# shield_uno.net
KiCad netlist of a schematic drawn in EAGLE
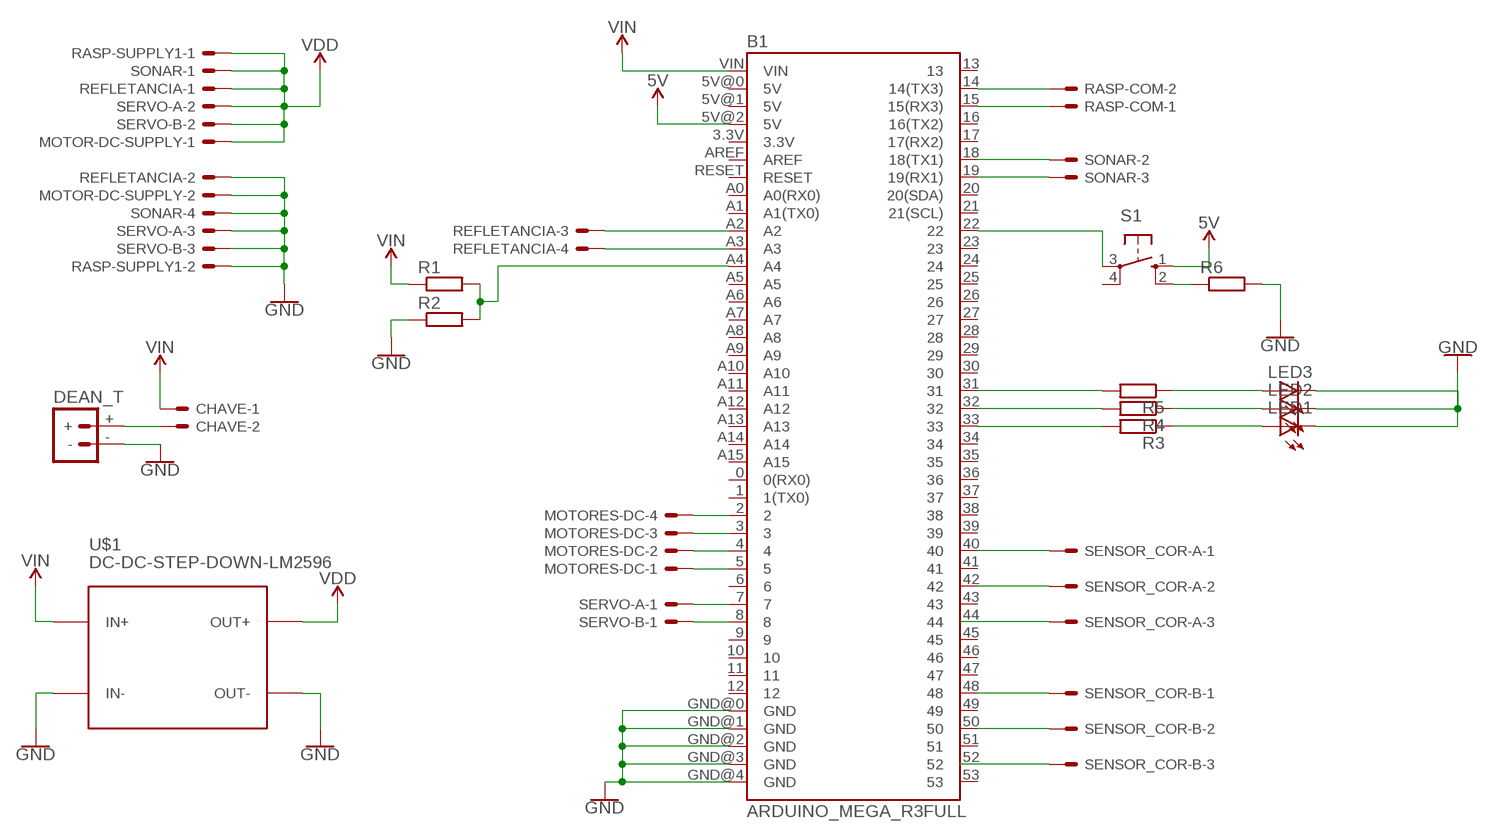
[diagram p0: schematic, sheet 1]

(export (version "E")
  (design (tool "Eeschema 10.0.6"))
  (components
    (comp (ref "B1")
      (value "ARDUINO_MEGA_R3FULL")
      (footprint "eagle-import:ARDUINO_MEGA")
      (libsource (lib "eagle-import") (part "ARDUINO_MEGA_R3FULL"))
    )
    (comp (ref "CHAVE")
      (value "22-23-2021")
      (footprint "eagle-import:22-23-2021")
      (fields (field (name "MF") "MOLEX"))
      (libsource (lib "eagle-import") (part "22-23-2021"))
    )
    (comp (ref "DEAN_T")
      (value "BATTERY_CONN_DEANS")
      (footprint "eagle-import:DEANS")
      (libsource (lib "eagle-import") (part "BATTERY_CONN_DEANS"))
    )
    (comp (ref "LED1")
      (value "LED5MM")
      (footprint "eagle-import:LED5MM")
      (libsource (lib "eagle-import") (part "LED5MM"))
    )
    (comp (ref "LED2")
      (value "LED5MM")
      (footprint "eagle-import:LED5MM")
      (libsource (lib "eagle-import") (part "LED5MM"))
    )
    (comp (ref "LED3")
      (value "LED5MM")
      (footprint "eagle-import:LED5MM")
      (libsource (lib "eagle-import") (part "LED5MM"))
    )
    (comp (ref "MOTOR-DC-SUPPLY")
      (value "22-23-2021")
      (footprint "eagle-import:22-23-2021")
      (fields (field (name "MF") "MOLEX"))
      (libsource (lib "eagle-import") (part "22-23-2021"))
    )
    (comp (ref "MOTORES-DC")
      (value "22-23-2041")
      (footprint "eagle-import:22-23-2041")
      (fields (field (name "MF") "MOLEX"))
      (libsource (lib "eagle-import") (part "22-23-2041"))
    )
    (comp (ref "R1")
      (value "R-EU_0207/12")
      (footprint "eagle-import:0207_12")
      (libsource (lib "eagle-import") (part "R-EU_0207/12"))
    )
    (comp (ref "R2")
      (value "R-EU_0207/12")
      (footprint "eagle-import:0207_12")
      (libsource (lib "eagle-import") (part "R-EU_0207/12"))
    )
    (comp (ref "R3")
      (value "R-EU_0207/7")
      (footprint "eagle-import:0207_7")
      (libsource (lib "eagle-import") (part "R-EU_0207/7"))
    )
    (comp (ref "R4")
      (value "R-EU_0207/7")
      (footprint "eagle-import:0207_7")
      (libsource (lib "eagle-import") (part "R-EU_0207/7"))
    )
    (comp (ref "R5")
      (value "R-EU_0207/7")
      (footprint "eagle-import:0207_7")
      (libsource (lib "eagle-import") (part "R-EU_0207/7"))
    )
    (comp (ref "R6")
      (value "R-EU_0204/5")
      (footprint "eagle-import:0204_5")
      (libsource (lib "eagle-import") (part "R-EU_0204/5"))
    )
    (comp (ref "RASP-COM")
      (value "22-23-2021")
      (footprint "eagle-import:22-23-2021")
      (fields (field (name "MF") "MOLEX"))
      (libsource (lib "eagle-import") (part "22-23-2021"))
    )
    (comp (ref "RASP-SUPPLY1")
      (value "22-23-2021")
      (footprint "eagle-import:22-23-2021")
      (fields (field (name "MF") "MOLEX"))
      (libsource (lib "eagle-import") (part "22-23-2021"))
    )
    (comp (ref "REFLETANCIA")
      (value "22-23-2041")
      (footprint "eagle-import:22-23-2041")
      (fields (field (name "MF") "MOLEX"))
      (libsource (lib "eagle-import") (part "22-23-2041"))
    )
    (comp (ref "S1")
      (value "10-XX")
      (footprint "eagle-import:B3F-10XX")
      (fields (field (name "MPN") "B3F-1000"))
      (libsource (lib "eagle-import") (part "10-XX"))
    )
    (comp (ref "SENSOR_COR-A")
      (value "22-23-2031")
      (footprint "eagle-import:22-23-2031")
      (fields (field (name "MF") "MOLEX"))
      (libsource (lib "eagle-import") (part "22-23-2031"))
    )
    (comp (ref "SENSOR_COR-B")
      (value "22-23-2031")
      (footprint "eagle-import:22-23-2031")
      (fields (field (name "MF") "MOLEX"))
      (libsource (lib "eagle-import") (part "22-23-2031"))
    )
    (comp (ref "SERVO-A")
      (value "22-23-2031")
      (footprint "eagle-import:22-23-2031")
      (fields (field (name "MF") "MOLEX"))
      (libsource (lib "eagle-import") (part "22-23-2031"))
    )
    (comp (ref "SERVO-B")
      (value "22-23-2031")
      (footprint "eagle-import:22-23-2031")
      (fields (field (name "MF") "MOLEX"))
      (libsource (lib "eagle-import") (part "22-23-2031"))
    )
    (comp (ref "SONAR")
      (value "22-23-2041")
      (footprint "eagle-import:22-23-2041")
      (fields (field (name "MF") "MOLEX"))
      (libsource (lib "eagle-import") (part "22-23-2041"))
    )
    (comp (ref "U$1")
      (value "DC-DC-STEP-DOWN-LM2596")
      (footprint "eagle-import:DC-DC-STEP-DOWN-LM2596")
      (libsource (lib "eagle-import") (part "DC-DC-STEP-DOWN-LM2596"))
    )
  )
  (nets
    (net (code "1") (name "5V") (class "Default")
      (node (ref "B1") (pin "5V@2") (pinfunction "5V_5V@2") (pintype "bidirectional"))
      (node (ref "S1") (pin "1") (pinfunction "S_1") (pintype "passive"))
    )
    (net (code "2") (name "GND") (class "Default")
      (node (ref "B1") (pin "GND@0") (pinfunction "GND_GND@0") (pintype "bidirectional"))
      (node (ref "B1") (pin "GND@1") (pinfunction "GND_GND@1") (pintype "bidirectional"))
      (node (ref "B1") (pin "GND@2") (pinfunction "GND_GND@2") (pintype "bidirectional"))
      (node (ref "B1") (pin "GND@3") (pinfunction "GND_GND@3") (pintype "bidirectional"))
      (node (ref "B1") (pin "GND@4") (pinfunction "GND_GND@4") (pintype "bidirectional"))
      (node (ref "DEAN_T") (pin "-") (pinfunction "-_-") (pintype "passive"))
      (node (ref "LED1") (pin "K") (pinfunction "C_K") (pintype "passive"))
      (node (ref "LED2") (pin "K") (pinfunction "C_K") (pintype "passive"))
      (node (ref "LED3") (pin "K") (pinfunction "C_K") (pintype "passive"))
      (node (ref "MOTOR-DC-SUPPLY") (pin "2") (pinfunction "S_2") (pintype "passive"))
      (node (ref "R2") (pin "1") (pinfunction "1_1") (pintype "passive"))
      (node (ref "R6") (pin "2") (pinfunction "2_2") (pintype "passive"))
      (node (ref "RASP-SUPPLY1") (pin "2") (pinfunction "S_2") (pintype "passive"))
      (node (ref "REFLETANCIA") (pin "2") (pinfunction "S_2") (pintype "passive"))
      (node (ref "SERVO-A") (pin "3") (pinfunction "S_3") (pintype "passive"))
      (node (ref "SERVO-B") (pin "3") (pinfunction "S_3") (pintype "passive"))
      (node (ref "SONAR") (pin "4") (pinfunction "S_4") (pintype "passive"))
      (node (ref "U$1") (pin "IN-") (pinfunction "IN-_IN-") (pintype "bidirectional"))
      (node (ref "U$1") (pin "OUT-") (pinfunction "OUT-_OUT-") (pintype "bidirectional"))
    )
    (net (code "3") (name "Net-(B1-14(TX3))") (class "Default")
      (node (ref "B1") (pin "14") (pinfunction "14(TX3)_14") (pintype "bidirectional"))
      (node (ref "RASP-COM") (pin "2") (pinfunction "S_2") (pintype "passive"))
    )
    (net (code "4") (name "Net-(B1-15(RX3))") (class "Default")
      (node (ref "B1") (pin "15") (pinfunction "15(RX3)_15") (pintype "bidirectional"))
      (node (ref "RASP-COM") (pin "1") (pinfunction "S_1") (pintype "passive"))
    )
    (net (code "5") (name "Net-(B1-18(TX1))") (class "Default")
      (node (ref "B1") (pin "18") (pinfunction "18(TX1)_18") (pintype "bidirectional"))
      (node (ref "SONAR") (pin "2") (pinfunction "S_2") (pintype "passive"))
    )
    (net (code "6") (name "Net-(B1-19(RX1))") (class "Default")
      (node (ref "B1") (pin "19") (pinfunction "19(RX1)_19") (pintype "bidirectional"))
      (node (ref "SONAR") (pin "3") (pinfunction "S_3") (pintype "passive"))
    )
    (net (code "7") (name "Net-(B1-Pad31)") (class "Default")
      (node (ref "B1") (pin "31") (pinfunction "31_31") (pintype "bidirectional"))
      (node (ref "R5") (pin "2") (pinfunction "2_2") (pintype "passive"))
    )
    (net (code "8") (name "Net-(B1-Pad32)") (class "Default")
      (node (ref "B1") (pin "32") (pinfunction "32_32") (pintype "bidirectional"))
      (node (ref "R4") (pin "2") (pinfunction "2_2") (pintype "passive"))
    )
    (net (code "9") (name "Net-(B1-Pad33)") (class "Default")
      (node (ref "B1") (pin "33") (pinfunction "33_33") (pintype "bidirectional"))
      (node (ref "R3") (pin "2") (pinfunction "2_2") (pintype "passive"))
    )
    (net (code "10") (name "Net-(B1-PadA4)") (class "Default")
      (node (ref "B1") (pin "A4") (pinfunction "A4_A4") (pintype "bidirectional"))
      (node (ref "R1") (pin "2") (pinfunction "2_2") (pintype "passive"))
      (node (ref "R2") (pin "2") (pinfunction "2_2") (pintype "passive"))
    )
    (net (code "11") (name "Net-(CHAVEB-S)") (class "Default")
      (node (ref "CHAVE") (pin "2") (pinfunction "S_2") (pintype "passive"))
      (node (ref "DEAN_T") (pin "+") (pinfunction "+_+") (pintype "passive"))
    )
    (net (code "12") (name "Net-(LED1-PadA)") (class "Default")
      (node (ref "LED1") (pin "A") (pinfunction "A_A") (pintype "passive"))
      (node (ref "R3") (pin "1") (pinfunction "1_1") (pintype "passive"))
    )
    (net (code "13") (name "Net-(LED2-PadA)") (class "Default")
      (node (ref "LED2") (pin "A") (pinfunction "A_A") (pintype "passive"))
      (node (ref "R4") (pin "1") (pinfunction "1_1") (pintype "passive"))
    )
    (net (code "14") (name "Net-(LED3-PadA)") (class "Default")
      (node (ref "LED3") (pin "A") (pinfunction "A_A") (pintype "passive"))
      (node (ref "R5") (pin "1") (pinfunction "1_1") (pintype "passive"))
    )
    (net (code "15") (name "Net-(MOTORES-DCA-S)") (class "Default")
      (node (ref "B1") (pin "5") (pinfunction "5_5") (pintype "bidirectional"))
      (node (ref "MOTORES-DC") (pin "1") (pinfunction "S_1") (pintype "passive"))
    )
    (net (code "16") (name "Net-(MOTORES-DCB-S)") (class "Default")
      (node (ref "B1") (pin "4") (pinfunction "4_4") (pintype "bidirectional"))
      (node (ref "MOTORES-DC") (pin "2") (pinfunction "S_2") (pintype "passive"))
    )
    (net (code "17") (name "Net-(MOTORES-DCC-S)") (class "Default")
      (node (ref "B1") (pin "3") (pinfunction "3_3") (pintype "bidirectional"))
      (node (ref "MOTORES-DC") (pin "3") (pinfunction "S_3") (pintype "passive"))
    )
    (net (code "18") (name "Net-(MOTORES-DCD-S)") (class "Default")
      (node (ref "B1") (pin "2") (pinfunction "2_2") (pintype "bidirectional"))
      (node (ref "MOTORES-DC") (pin "4") (pinfunction "S_4") (pintype "passive"))
    )
    (net (code "19") (name "Net-(REFLETANCIAC-S)") (class "Default")
      (node (ref "B1") (pin "A2") (pinfunction "A2_A2") (pintype "bidirectional"))
      (node (ref "REFLETANCIA") (pin "3") (pinfunction "S_3") (pintype "passive"))
    )
    (net (code "20") (name "Net-(REFLETANCIAD-S)") (class "Default")
      (node (ref "B1") (pin "A3") (pinfunction "A3_A3") (pintype "bidirectional"))
      (node (ref "REFLETANCIA") (pin "4") (pinfunction "S_4") (pintype "passive"))
    )
    (net (code "21") (name "Net-(S1-P)") (class "Default")
      (node (ref "B1") (pin "22") (pinfunction "22_22") (pintype "bidirectional"))
      (node (ref "S1") (pin "3") (pinfunction "P_3") (pintype "passive"))
    )
    (net (code "22") (name "Net-(S1-S1)") (class "Default")
      (node (ref "R6") (pin "1") (pinfunction "1_1") (pintype "passive"))
      (node (ref "S1") (pin "2") (pinfunction "S1_2") (pintype "passive"))
    )
    (net (code "23") (name "Net-(SENSOR_COR-AA-S)") (class "Default")
      (node (ref "B1") (pin "40") (pinfunction "40_40") (pintype "bidirectional"))
      (node (ref "SENSOR_COR-A") (pin "1") (pinfunction "S_1") (pintype "passive"))
    )
    (net (code "24") (name "Net-(SENSOR_COR-AB-S)") (class "Default")
      (node (ref "B1") (pin "42") (pinfunction "42_42") (pintype "bidirectional"))
      (node (ref "SENSOR_COR-A") (pin "2") (pinfunction "S_2") (pintype "passive"))
    )
    (net (code "25") (name "Net-(SENSOR_COR-BA-S)") (class "Default")
      (node (ref "B1") (pin "48") (pinfunction "48_48") (pintype "bidirectional"))
      (node (ref "SENSOR_COR-B") (pin "1") (pinfunction "S_1") (pintype "passive"))
    )
    (net (code "26") (name "Net-(SENSOR_COR-BB-S)") (class "Default")
      (node (ref "B1") (pin "50") (pinfunction "50_50") (pintype "bidirectional"))
      (node (ref "SENSOR_COR-B") (pin "2") (pinfunction "S_2") (pintype "passive"))
    )
    (net (code "27") (name "Net-(SERVO-AA-S)") (class "Default")
      (node (ref "B1") (pin "7") (pinfunction "7_7") (pintype "bidirectional"))
      (node (ref "SERVO-A") (pin "1") (pinfunction "S_1") (pintype "passive"))
    )
    (net (code "28") (name "Net-(SERVO-BA-S)") (class "Default")
      (node (ref "B1") (pin "8") (pinfunction "8_8") (pintype "bidirectional"))
      (node (ref "SERVO-B") (pin "1") (pinfunction "S_1") (pintype "passive"))
    )
    (net (code "29") (name "VDD") (class "Default")
      (node (ref "MOTOR-DC-SUPPLY") (pin "1") (pinfunction "S_1") (pintype "passive"))
      (node (ref "RASP-SUPPLY1") (pin "1") (pinfunction "S_1") (pintype "passive"))
      (node (ref "REFLETANCIA") (pin "1") (pinfunction "S_1") (pintype "passive"))
      (node (ref "SERVO-A") (pin "2") (pinfunction "S_2") (pintype "passive"))
      (node (ref "SERVO-B") (pin "2") (pinfunction "S_2") (pintype "passive"))
      (node (ref "SONAR") (pin "1") (pinfunction "S_1") (pintype "passive"))
      (node (ref "U$1") (pin "OUT+") (pinfunction "OUT+_OUT+") (pintype "bidirectional"))
    )
    (net (code "30") (name "VIN") (class "Default")
      (node (ref "B1") (pin "VIN") (pinfunction "VIN_VIN") (pintype "bidirectional"))
      (node (ref "CHAVE") (pin "1") (pinfunction "S_1") (pintype "passive"))
      (node (ref "R1") (pin "1") (pinfunction "1_1") (pintype "passive"))
      (node (ref "U$1") (pin "IN+") (pinfunction "IN+_IN+") (pintype "bidirectional"))
    )
    (net (code "31") (name "unconnected-(B1-0(RX0)-Pad0)") (class "Default")
      (node (ref "B1") (pin "0") (pinfunction "0(RX0)_0") (pintype "bidirectional"))
    )
    (net (code "32") (name "unconnected-(B1-1(TX0)-Pad1)") (class "Default")
      (node (ref "B1") (pin "1") (pinfunction "1(TX0)_1") (pintype "bidirectional"))
    )
    (net (code "33") (name "unconnected-(B1-5V-Pad5V@0)") (class "Default")
      (node (ref "B1") (pin "5V@0") (pinfunction "5V_5V@0") (pintype "bidirectional"))
    )
    (net (code "34") (name "unconnected-(B1-5V-Pad5V@1)") (class "Default")
      (node (ref "B1") (pin "5V@1") (pinfunction "5V_5V@1") (pintype "bidirectional"))
    )
    (net (code "35") (name "unconnected-(B1-16(TX2)-Pad16)") (class "Default")
      (node (ref "B1") (pin "16") (pinfunction "16(TX2)_16") (pintype "bidirectional"))
    )
    (net (code "36") (name "unconnected-(B1-17(RX2)-Pad17)") (class "Default")
      (node (ref "B1") (pin "17") (pinfunction "17(RX2)_17") (pintype "bidirectional"))
    )
    (net (code "37") (name "unconnected-(B1-20(SDA)-Pad20)") (class "Default")
      (node (ref "B1") (pin "20") (pinfunction "20(SDA)_20") (pintype "bidirectional"))
    )
    (net (code "38") (name "unconnected-(B1-21(SCL)-Pad21)") (class "Default")
      (node (ref "B1") (pin "21") (pinfunction "21(SCL)_21") (pintype "bidirectional"))
    )
    (net (code "39") (name "unconnected-(B1-A0(RX0)-PadA0)") (class "Default")
      (node (ref "B1") (pin "A0") (pinfunction "A0(RX0)_A0") (pintype "bidirectional"))
    )
    (net (code "40") (name "unconnected-(B1-A1(TX0)-PadA1)") (class "Default")
      (node (ref "B1") (pin "A1") (pinfunction "A1(TX0)_A1") (pintype "bidirectional"))
    )
    (net (code "41") (name "unconnected-(B1-Pad3.3V)") (class "Default")
      (node (ref "B1") (pin "3.3V") (pinfunction "3.3V_3.3V") (pintype "bidirectional"))
    )
    (net (code "42") (name "unconnected-(B1-Pad6)") (class "Default")
      (node (ref "B1") (pin "6") (pinfunction "6_6") (pintype "bidirectional"))
    )
    (net (code "43") (name "unconnected-(B1-Pad9)") (class "Default")
      (node (ref "B1") (pin "9") (pinfunction "9_9") (pintype "bidirectional"))
    )
    (net (code "44") (name "unconnected-(B1-Pad10)") (class "Default")
      (node (ref "B1") (pin "10") (pinfunction "10_10") (pintype "bidirectional"))
    )
    (net (code "45") (name "unconnected-(B1-Pad11)") (class "Default")
      (node (ref "B1") (pin "11") (pinfunction "11_11") (pintype "bidirectional"))
    )
    (net (code "46") (name "unconnected-(B1-Pad12)") (class "Default")
      (node (ref "B1") (pin "12") (pinfunction "12_12") (pintype "bidirectional"))
    )
    (net (code "47") (name "unconnected-(B1-Pad13)") (class "Default")
      (node (ref "B1") (pin "13") (pinfunction "13_13") (pintype "bidirectional"))
    )
    (net (code "48") (name "unconnected-(B1-Pad23)") (class "Default")
      (node (ref "B1") (pin "23") (pinfunction "23_23") (pintype "bidirectional"))
    )
    (net (code "49") (name "unconnected-(B1-Pad24)") (class "Default")
      (node (ref "B1") (pin "24") (pinfunction "24_24") (pintype "bidirectional"))
    )
    (net (code "50") (name "unconnected-(B1-Pad25)") (class "Default")
      (node (ref "B1") (pin "25") (pinfunction "25_25") (pintype "bidirectional"))
    )
    (net (code "51") (name "unconnected-(B1-Pad26)") (class "Default")
      (node (ref "B1") (pin "26") (pinfunction "26_26") (pintype "bidirectional"))
    )
    (net (code "52") (name "unconnected-(B1-Pad27)") (class "Default")
      (node (ref "B1") (pin "27") (pinfunction "27_27") (pintype "bidirectional"))
    )
    (net (code "53") (name "unconnected-(B1-Pad28)") (class "Default")
      (node (ref "B1") (pin "28") (pinfunction "28_28") (pintype "bidirectional"))
    )
    (net (code "54") (name "unconnected-(B1-Pad29)") (class "Default")
      (node (ref "B1") (pin "29") (pinfunction "29_29") (pintype "bidirectional"))
    )
    (net (code "55") (name "unconnected-(B1-Pad30)") (class "Default")
      (node (ref "B1") (pin "30") (pinfunction "30_30") (pintype "bidirectional"))
    )
    (net (code "56") (name "unconnected-(B1-Pad34)") (class "Default")
      (node (ref "B1") (pin "34") (pinfunction "34_34") (pintype "bidirectional"))
    )
    (net (code "57") (name "unconnected-(B1-Pad35)") (class "Default")
      (node (ref "B1") (pin "35") (pinfunction "35_35") (pintype "bidirectional"))
    )
    (net (code "58") (name "unconnected-(B1-Pad36)") (class "Default")
      (node (ref "B1") (pin "36") (pinfunction "36_36") (pintype "bidirectional"))
    )
    (net (code "59") (name "unconnected-(B1-Pad37)") (class "Default")
      (node (ref "B1") (pin "37") (pinfunction "37_37") (pintype "bidirectional"))
    )
    (net (code "60") (name "unconnected-(B1-Pad38)") (class "Default")
      (node (ref "B1") (pin "38") (pinfunction "38_38") (pintype "bidirectional"))
    )
    (net (code "61") (name "unconnected-(B1-Pad39)") (class "Default")
      (node (ref "B1") (pin "39") (pinfunction "39_39") (pintype "bidirectional"))
    )
    (net (code "62") (name "unconnected-(B1-Pad41)") (class "Default")
      (node (ref "B1") (pin "41") (pinfunction "41_41") (pintype "bidirectional"))
    )
    (net (code "63") (name "unconnected-(B1-Pad43)") (class "Default")
      (node (ref "B1") (pin "43") (pinfunction "43_43") (pintype "bidirectional"))
    )
    (net (code "64") (name "unconnected-(B1-Pad44)") (class "Default")
      (node (ref "B1") (pin "44") (pinfunction "44_44") (pintype "bidirectional"))
    )
    (net (code "65") (name "unconnected-(B1-Pad45)") (class "Default")
      (node (ref "B1") (pin "45") (pinfunction "45_45") (pintype "bidirectional"))
    )
    (net (code "66") (name "unconnected-(B1-Pad46)") (class "Default")
      (node (ref "B1") (pin "46") (pinfunction "46_46") (pintype "bidirectional"))
    )
    (net (code "67") (name "unconnected-(B1-Pad47)") (class "Default")
      (node (ref "B1") (pin "47") (pinfunction "47_47") (pintype "bidirectional"))
    )
    (net (code "68") (name "unconnected-(B1-Pad49)") (class "Default")
      (node (ref "B1") (pin "49") (pinfunction "49_49") (pintype "bidirectional"))
    )
    (net (code "69") (name "unconnected-(B1-Pad51)") (class "Default")
      (node (ref "B1") (pin "51") (pinfunction "51_51") (pintype "bidirectional"))
    )
    (net (code "70") (name "unconnected-(B1-Pad52)") (class "Default")
      (node (ref "B1") (pin "52") (pinfunction "52_52") (pintype "bidirectional"))
    )
    (net (code "71") (name "unconnected-(B1-Pad53)") (class "Default")
      (node (ref "B1") (pin "53") (pinfunction "53_53") (pintype "bidirectional"))
    )
    (net (code "72") (name "unconnected-(B1-PadA5)") (class "Default")
      (node (ref "B1") (pin "A5") (pinfunction "A5_A5") (pintype "bidirectional"))
    )
    (net (code "73") (name "unconnected-(B1-PadA6)") (class "Default")
      (node (ref "B1") (pin "A6") (pinfunction "A6_A6") (pintype "bidirectional"))
    )
    (net (code "74") (name "unconnected-(B1-PadA7)") (class "Default")
      (node (ref "B1") (pin "A7") (pinfunction "A7_A7") (pintype "bidirectional"))
    )
    (net (code "75") (name "unconnected-(B1-PadA8)") (class "Default")
      (node (ref "B1") (pin "A8") (pinfunction "A8_A8") (pintype "bidirectional"))
    )
    (net (code "76") (name "unconnected-(B1-PadA9)") (class "Default")
      (node (ref "B1") (pin "A9") (pinfunction "A9_A9") (pintype "bidirectional"))
    )
    (net (code "77") (name "unconnected-(B1-PadA10)") (class "Default")
      (node (ref "B1") (pin "A10") (pinfunction "A10_A10") (pintype "bidirectional"))
    )
    (net (code "78") (name "unconnected-(B1-PadA11)") (class "Default")
      (node (ref "B1") (pin "A11") (pinfunction "A11_A11") (pintype "bidirectional"))
    )
    (net (code "79") (name "unconnected-(B1-PadA12)") (class "Default")
      (node (ref "B1") (pin "A12") (pinfunction "A12_A12") (pintype "bidirectional"))
    )
    (net (code "80") (name "unconnected-(B1-PadA13)") (class "Default")
      (node (ref "B1") (pin "A13") (pinfunction "A13_A13") (pintype "bidirectional"))
    )
    (net (code "81") (name "unconnected-(B1-PadA14)") (class "Default")
      (node (ref "B1") (pin "A14") (pinfunction "A14_A14") (pintype "bidirectional"))
    )
    (net (code "82") (name "unconnected-(B1-PadA15)") (class "Default")
      (node (ref "B1") (pin "A15") (pinfunction "A15_A15") (pintype "bidirectional"))
    )
    (net (code "83") (name "unconnected-(B1-PadAREF)") (class "Default")
      (node (ref "B1") (pin "AREF") (pinfunction "AREF_AREF") (pintype "bidirectional"))
    )
    (net (code "84") (name "unconnected-(B1-PadRESET)") (class "Default")
      (node (ref "B1") (pin "RESET") (pinfunction "RESET_RESET") (pintype "bidirectional"))
    )
    (net (code "85") (name "unconnected-(S1-P1-Pad4)") (class "Default")
      (node (ref "S1") (pin "4") (pinfunction "P1_4") (pintype "passive"))
    )
    (net (code "86") (name "unconnected-(SENSOR_COR-AC-S-Pad3)") (class "Default")
      (node (ref "SENSOR_COR-A") (pin "3") (pinfunction "S_3") (pintype "passive"))
    )
    (net (code "87") (name "unconnected-(SENSOR_COR-BC-S-Pad3)") (class "Default")
      (node (ref "SENSOR_COR-B") (pin "3") (pinfunction "S_3") (pintype "passive"))
    )
  )
)
